# DCO_DIL14.net
KiCad netlist of a schematic drawn in EAGLE
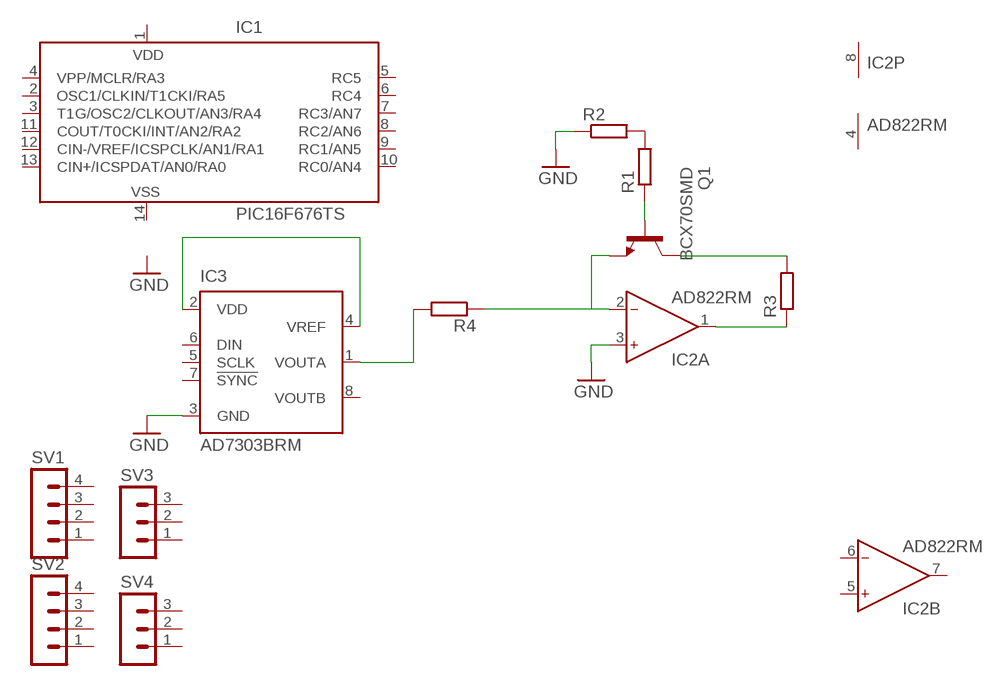
[diagram p0: schematic, sheet 1]

(export (version "E")
  (design (tool "Eeschema 10.0.6"))
  (components
    (comp (ref "IC1")
      (value "PIC16F676TS")
      (footprint "eagle-import:TSSOP14")
      (fields (field (name "MF") "MICROCHIP") (field (name "MPN") "PIC16F676-E/ST"))
      (libsource (lib "eagle-import") (part "PIC16F676TS"))
    )
    (comp (ref "IC2")
      (value "AD822RM")
      (footprint "eagle-import:MSOP08")
      (fields (field (name "MPN") "AD822ARMZ-R2"))
      (libsource (lib "eagle-import") (part "AD822RM"))
    )
    (comp (ref "IC3")
      (value "AD7303BRM")
      (footprint "eagle-import:MSOP08")
      (fields (field (name "MF") "ALTERA CORPORATION") (field (name "MPN") "AD7303BRMZ"))
      (libsource (lib "eagle-import") (part "AD7303BRM"))
    )
    (comp (ref "Q1")
      (value "BCX70SMD")
      (footprint "eagle-import:SOT23")
      (libsource (lib "eagle-import") (part "BCX70SMD"))
    )
    (comp (ref "R1")
      (value "R-EU_R0603")
      (footprint "eagle-import:R0603")
      (libsource (lib "eagle-import") (part "R-EU_R0603"))
    )
    (comp (ref "R2")
      (value "R-EU_R0603")
      (footprint "eagle-import:R0603")
      (libsource (lib "eagle-import") (part "R-EU_R0603"))
    )
    (comp (ref "R3")
      (value "R-EU_R0603")
      (footprint "eagle-import:R0603")
      (libsource (lib "eagle-import") (part "R-EU_R0603"))
    )
    (comp (ref "R4")
      (value "R-EU_R0603")
      (footprint "eagle-import:R0603")
      (libsource (lib "eagle-import") (part "R-EU_R0603"))
    )
    (comp (ref "SV1")
      (value "MA04-1J")
      (footprint "eagle-import:MA04-1J")
      (libsource (lib "eagle-import") (part "MA04-1J"))
    )
    (comp (ref "SV2")
      (value "MA04-1J")
      (footprint "eagle-import:MA04-1J")
      (libsource (lib "eagle-import") (part "MA04-1J"))
    )
    (comp (ref "SV3")
      (value "MA03-1J")
      (footprint "eagle-import:MA03-1J")
      (libsource (lib "eagle-import") (part "MA03-1J"))
    )
    (comp (ref "SV4")
      (value "MA03-1J")
      (footprint "eagle-import:MA03-1J")
      (libsource (lib "eagle-import") (part "MA03-1J"))
    )
  )
  (nets
    (net (code "1") (name "/V+") (class "Default")
      (node (ref "IC2") (pin "8") (pinfunction "V+_8") (pintype "power_in"))
    )
    (net (code "2") (name "/V-") (class "Default")
      (node (ref "IC2") (pin "4") (pinfunction "V-_4") (pintype "power_in"))
    )
    (net (code "3") (name "/VDD") (class "Default")
      (node (ref "IC1") (pin "1") (pinfunction "VDD_1") (pintype "power_in"))
    )
    (net (code "4") (name "/VSS") (class "Default")
      (node (ref "IC1") (pin "14") (pinfunction "VSS_14") (pintype "power_in"))
    )
    (net (code "5") (name "GND") (class "Default")
      (node (ref "IC2") (pin "3") (pinfunction "IN+_3") (pintype "input"))
      (node (ref "IC3") (pin "3") (pinfunction "GND_3") (pintype "power_in"))
      (node (ref "R2") (pin "1") (pinfunction "1_1") (pintype "passive"))
    )
    (net (code "6") (name "Net-(IC2A-IN-)") (class "Default")
      (node (ref "IC2") (pin "2") (pinfunction "IN-_2") (pintype "input"))
      (node (ref "Q1") (pin "2") (pinfunction "E_2") (pintype "passive"))
      (node (ref "R4") (pin "1") (pinfunction "1_1") (pintype "passive"))
    )
    (net (code "7") (name "Net-(IC2A-OUT)") (class "Default")
      (node (ref "IC2") (pin "1") (pinfunction "OUT_1") (pintype "output"))
      (node (ref "R3") (pin "1") (pinfunction "1_1") (pintype "passive"))
    )
    (net (code "8") (name "Net-(IC3-VDD)") (class "Default")
      (node (ref "IC3") (pin "2") (pinfunction "VDD_2") (pintype "power_in"))
      (node (ref "IC3") (pin "4") (pinfunction "VREF_4") (pintype "passive"))
    )
    (net (code "9") (name "Net-(IC3-VOUTA)") (class "Default")
      (node (ref "IC3") (pin "1") (pinfunction "VOUTA_1") (pintype "output"))
      (node (ref "R4") (pin "2") (pinfunction "2_2") (pintype "passive"))
    )
    (net (code "10") (name "Net-(Q1-B)") (class "Default")
      (node (ref "Q1") (pin "1") (pinfunction "B_1") (pintype "passive"))
      (node (ref "R1") (pin "1") (pinfunction "1_1") (pintype "passive"))
    )
    (net (code "11") (name "Net-(Q1-C)") (class "Default")
      (node (ref "Q1") (pin "3") (pinfunction "C_3") (pintype "passive"))
      (node (ref "R3") (pin "2") (pinfunction "2_2") (pintype "passive"))
    )
    (net (code "12") (name "Net-(R1-Pad2)") (class "Default")
      (node (ref "R1") (pin "2") (pinfunction "2_2") (pintype "passive"))
      (node (ref "R2") (pin "2") (pinfunction "2_2") (pintype "passive"))
    )
    (net (code "13") (name "unconnected-(IC1-CIN+{slash}ICSPDAT{slash}AN0{slash}RA0-Pad13)") (class "Default")
      (node (ref "IC1") (pin "13") (pinfunction "CIN+/ICSPDAT/AN0/RA0_13") (pintype "bidirectional"))
    )
    (net (code "14") (name "unconnected-(IC1-CIN-{slash}VREF{slash}ICSPCLK{slash}AN1{slash}RA1-Pad12)") (class "Default")
      (node (ref "IC1") (pin "12") (pinfunction "CIN-/VREF/ICSPCLK/AN1/RA1_12") (pintype "bidirectional"))
    )
    (net (code "15") (name "unconnected-(IC1-COUT{slash}T0CKI{slash}INT{slash}AN2{slash}RA2-Pad11)") (class "Default")
      (node (ref "IC1") (pin "11") (pinfunction "COUT/T0CKI/INT/AN2/RA2_11") (pintype "bidirectional"))
    )
    (net (code "16") (name "unconnected-(IC1-OSC1{slash}CLKIN{slash}T1CKI{slash}RA5-Pad2)") (class "Default")
      (node (ref "IC1") (pin "2") (pinfunction "OSC1/CLKIN/T1CKI/RA5_2") (pintype "bidirectional"))
    )
    (net (code "17") (name "unconnected-(IC1-RC0{slash}AN4-Pad10)") (class "Default")
      (node (ref "IC1") (pin "10") (pinfunction "RC0/AN4_10") (pintype "bidirectional"))
    )
    (net (code "18") (name "unconnected-(IC1-RC1{slash}AN5-Pad9)") (class "Default")
      (node (ref "IC1") (pin "9") (pinfunction "RC1/AN5_9") (pintype "bidirectional"))
    )
    (net (code "19") (name "unconnected-(IC1-RC2{slash}AN6-Pad8)") (class "Default")
      (node (ref "IC1") (pin "8") (pinfunction "RC2/AN6_8") (pintype "bidirectional"))
    )
    (net (code "20") (name "unconnected-(IC1-RC3{slash}AN7-Pad7)") (class "Default")
      (node (ref "IC1") (pin "7") (pinfunction "RC3/AN7_7") (pintype "bidirectional"))
    )
    (net (code "21") (name "unconnected-(IC1-RC4-Pad6)") (class "Default")
      (node (ref "IC1") (pin "6") (pinfunction "RC4_6") (pintype "bidirectional"))
    )
    (net (code "22") (name "unconnected-(IC1-RC5-Pad5)") (class "Default")
      (node (ref "IC1") (pin "5") (pinfunction "RC5_5") (pintype "bidirectional"))
    )
    (net (code "23") (name "unconnected-(IC1-T1G{slash}OSC2{slash}CLKOUT{slash}AN3{slash}RA4-Pad3)") (class "Default")
      (node (ref "IC1") (pin "3") (pinfunction "T1G/OSC2/CLKOUT/AN3/RA4_3") (pintype "bidirectional"))
    )
    (net (code "24") (name "unconnected-(IC1-VPP{slash}MCLR{slash}RA3-Pad4)") (class "Default")
      (node (ref "IC1") (pin "4") (pinfunction "VPP/MCLR/RA3_4") (pintype "input"))
    )
    (net (code "25") (name "unconnected-(IC2B-IN+-Pad5)") (class "Default")
      (node (ref "IC2") (pin "5") (pinfunction "IN+_5") (pintype "input"))
    )
    (net (code "26") (name "unconnected-(IC2B-IN--Pad6)") (class "Default")
      (node (ref "IC2") (pin "6") (pinfunction "IN-_6") (pintype "input"))
    )
    (net (code "27") (name "unconnected-(IC2B-OUT-Pad7)") (class "Default")
      (node (ref "IC2") (pin "7") (pinfunction "OUT_7") (pintype "output"))
    )
    (net (code "28") (name "unconnected-(IC3-DIN-Pad6)") (class "Default")
      (node (ref "IC3") (pin "6") (pinfunction "DIN_6") (pintype "input"))
    )
    (net (code "29") (name "unconnected-(IC3-SCLK-Pad5)") (class "Default")
      (node (ref "IC3") (pin "5") (pinfunction "SCLK_5") (pintype "input"))
    )
    (net (code "30") (name "unconnected-(IC3-VOUTB-Pad8)") (class "Default")
      (node (ref "IC3") (pin "8") (pinfunction "VOUTB_8") (pintype "output"))
    )
    (net (code "31") (name "unconnected-(IC3-~{SYNC}-Pad7)") (class "Default")
      (node (ref "IC3") (pin "7") (pinfunction "~{SYNC}_7") (pintype "input"))
    )
    (net (code "32") (name "unconnected-(SV1-Pad1)") (class "Default")
      (node (ref "SV1") (pin "1") (pinfunction "1_1") (pintype "passive"))
    )
    (net (code "33") (name "unconnected-(SV1-Pad2)") (class "Default")
      (node (ref "SV1") (pin "2") (pinfunction "2_2") (pintype "passive"))
    )
    (net (code "34") (name "unconnected-(SV1-Pad3)") (class "Default")
      (node (ref "SV1") (pin "3") (pinfunction "3_3") (pintype "passive"))
    )
    (net (code "35") (name "unconnected-(SV1-Pad4)") (class "Default")
      (node (ref "SV1") (pin "4") (pinfunction "4_4") (pintype "passive"))
    )
    (net (code "36") (name "unconnected-(SV2-Pad1)") (class "Default")
      (node (ref "SV2") (pin "1") (pinfunction "1_1") (pintype "passive"))
    )
    (net (code "37") (name "unconnected-(SV2-Pad2)") (class "Default")
      (node (ref "SV2") (pin "2") (pinfunction "2_2") (pintype "passive"))
    )
    (net (code "38") (name "unconnected-(SV2-Pad3)") (class "Default")
      (node (ref "SV2") (pin "3") (pinfunction "3_3") (pintype "passive"))
    )
    (net (code "39") (name "unconnected-(SV2-Pad4)") (class "Default")
      (node (ref "SV2") (pin "4") (pinfunction "4_4") (pintype "passive"))
    )
    (net (code "40") (name "unconnected-(SV3-Pad1)") (class "Default")
      (node (ref "SV3") (pin "1") (pinfunction "1_1") (pintype "passive"))
    )
    (net (code "41") (name "unconnected-(SV3-Pad2)") (class "Default")
      (node (ref "SV3") (pin "2") (pinfunction "2_2") (pintype "passive"))
    )
    (net (code "42") (name "unconnected-(SV3-Pad3)") (class "Default")
      (node (ref "SV3") (pin "3") (pinfunction "3_3") (pintype "passive"))
    )
    (net (code "43") (name "unconnected-(SV4-Pad1)") (class "Default")
      (node (ref "SV4") (pin "1") (pinfunction "1_1") (pintype "passive"))
    )
    (net (code "44") (name "unconnected-(SV4-Pad2)") (class "Default")
      (node (ref "SV4") (pin "2") (pinfunction "2_2") (pintype "passive"))
    )
    (net (code "45") (name "unconnected-(SV4-Pad3)") (class "Default")
      (node (ref "SV4") (pin "3") (pinfunction "3_3") (pintype "passive"))
    )
  )
)
